# Kasli_SOC_IDC_EXT_Connectors.net
KiCad netlist of a schematic drawn in Altium Designer
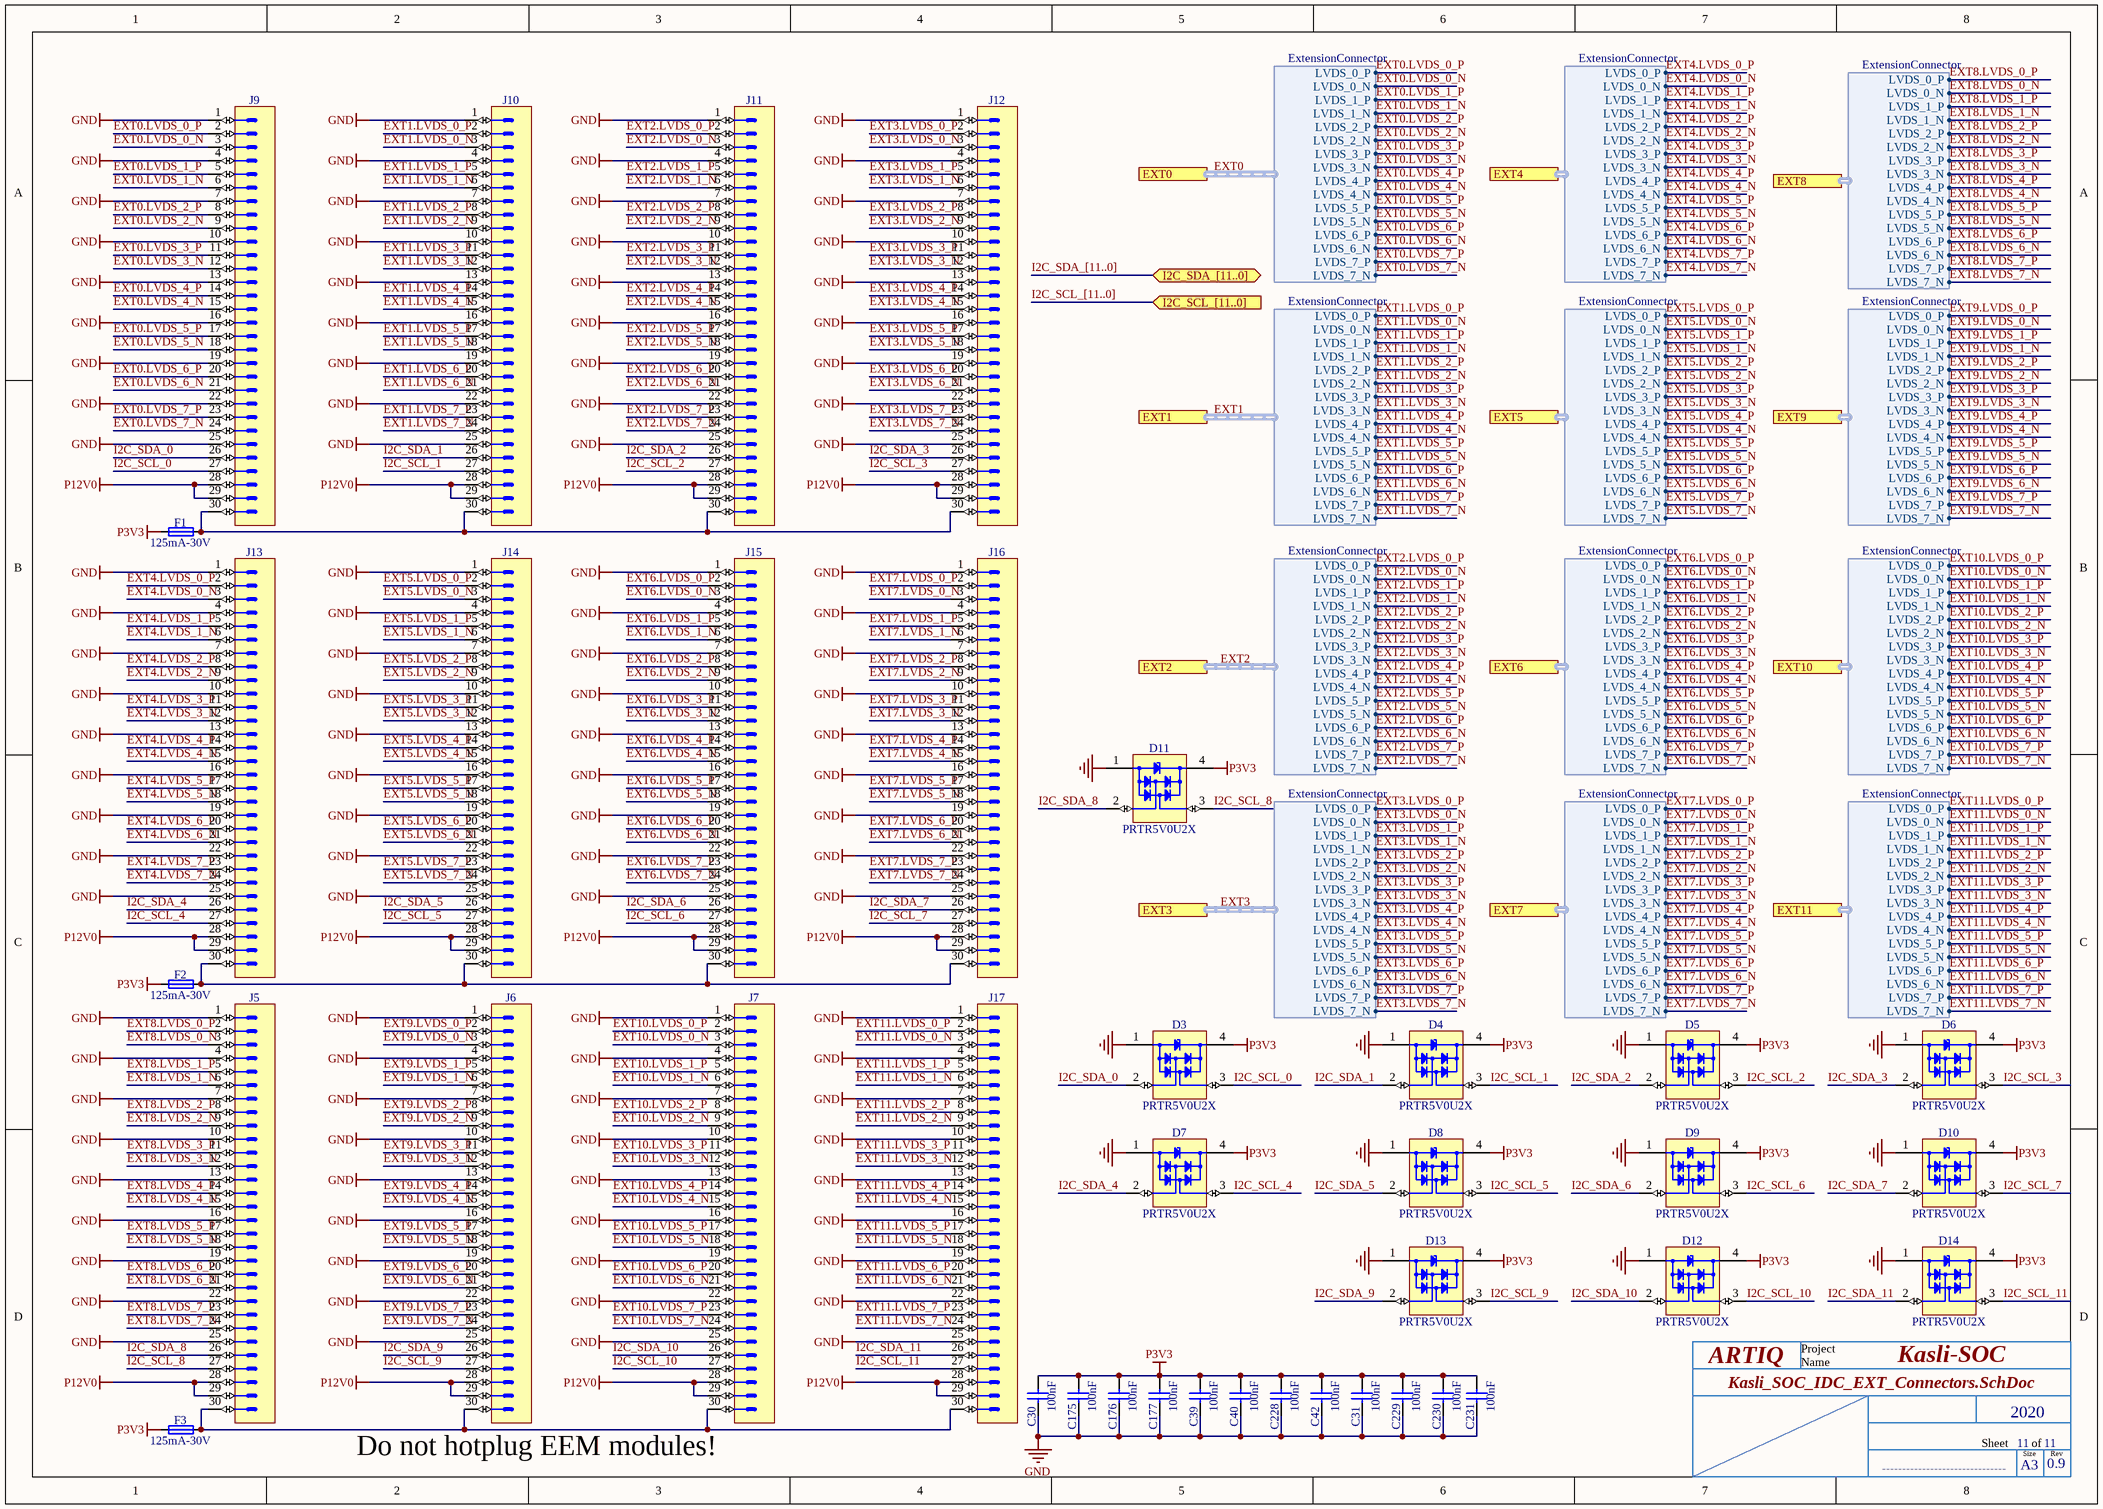
[diagram p0: Kasli_SOC_IDC_EXT_Connectors.SchDoc]

(export (version "E")
  (design (tool "Eeschema 10.0.6"))
  (components
    (comp (ref "C30")
      (value "100nF")
      (footprint "CAPC0603X33N")
      (description "Non-polarised capacitor")
      (fields
        (field (name "PART NUMBER") "CC0201_100NF_6.3V_10%_X5R")
        (field (name "VOLTAGE") "6.3V")
        (field (name "AUTHOR") "CERN DEM JLC")
      )
      (libsource (lib "Capacitors") (part "Capacitor - non polarized"))
    )
    (comp (ref "C31")
      (value "100nF")
      (footprint "CAPC0603X33N")
      (description "Non-polarised capacitor")
      (fields
        (field (name "PART NUMBER") "CC0201_100NF_6.3V_10%_X5R")
        (field (name "VOLTAGE") "6.3V")
        (field (name "AUTHOR") "CERN DEM JLC")
      )
      (libsource (lib "Capacitors") (part "Capacitor - non polarized"))
    )
    (comp (ref "C39")
      (value "100nF")
      (footprint "CAPC0603X33N")
      (description "Non-polarised capacitor")
      (fields
        (field (name "PART NUMBER") "CC0201_100NF_6.3V_10%_X5R")
        (field (name "VOLTAGE") "6.3V")
        (field (name "AUTHOR") "CERN DEM JLC")
      )
      (libsource (lib "Capacitors") (part "Capacitor - non polarized"))
    )
    (comp (ref "C40")
      (value "100nF")
      (footprint "CAPC0603X33N")
      (description "Non-polarised capacitor")
      (fields
        (field (name "PART NUMBER") "CC0201_100NF_6.3V_10%_X5R")
        (field (name "VOLTAGE") "6.3V")
        (field (name "AUTHOR") "CERN DEM JLC")
      )
      (libsource (lib "Capacitors") (part "Capacitor - non polarized"))
    )
    (comp (ref "C42")
      (value "100nF")
      (footprint "CAPC0603X33N")
      (description "Non-polarised capacitor")
      (fields
        (field (name "PART NUMBER") "CC0201_100NF_6.3V_10%_X5R")
        (field (name "VOLTAGE") "6.3V")
        (field (name "AUTHOR") "CERN DEM JLC")
      )
      (libsource (lib "Capacitors") (part "Capacitor - non polarized"))
    )
    (comp (ref "C175")
      (value "100nF")
      (footprint "CAPC0603X33N")
      (description "Non-polarised capacitor")
      (fields
        (field (name "PART NUMBER") "CC0201_100NF_6.3V_10%_X5R")
        (field (name "VOLTAGE") "6.3V")
        (field (name "AUTHOR") "CERN DEM JLC")
      )
      (libsource (lib "Capacitors") (part "Capacitor - non polarized"))
    )
    (comp (ref "C176")
      (value "100nF")
      (footprint "CAPC0603X33N")
      (description "Non-polarised capacitor")
      (fields
        (field (name "PART NUMBER") "CC0201_100NF_6.3V_10%_X5R")
        (field (name "VOLTAGE") "6.3V")
        (field (name "AUTHOR") "CERN DEM JLC")
      )
      (libsource (lib "Capacitors") (part "Capacitor - non polarized"))
    )
    (comp (ref "C177")
      (value "100nF")
      (footprint "CAPC0603X33N")
      (description "Non-polarised capacitor")
      (fields
        (field (name "PART NUMBER") "CC0201_100NF_6.3V_10%_X5R")
        (field (name "VOLTAGE") "6.3V")
        (field (name "AUTHOR") "CERN DEM JLC")
      )
      (libsource (lib "Capacitors") (part "Capacitor - non polarized"))
    )
    (comp (ref "C228")
      (value "100nF")
      (footprint "CAPC0603X33N")
      (description "Non-polarised capacitor")
      (fields
        (field (name "PART NUMBER") "CC0201_100NF_6.3V_10%_X5R")
        (field (name "VOLTAGE") "6.3V")
        (field (name "AUTHOR") "CERN DEM JLC")
      )
      (libsource (lib "Capacitors") (part "Capacitor - non polarized"))
    )
    (comp (ref "C229")
      (value "100nF")
      (footprint "CAPC0603X33N")
      (description "Non-polarised capacitor")
      (fields
        (field (name "PART NUMBER") "CC0201_100NF_6.3V_10%_X5R")
        (field (name "VOLTAGE") "6.3V")
        (field (name "AUTHOR") "CERN DEM JLC")
      )
      (libsource (lib "Capacitors") (part "Capacitor - non polarized"))
    )
    (comp (ref "C230")
      (value "100nF")
      (footprint "CAPC0603X33N")
      (description "Non-polarised capacitor")
      (fields
        (field (name "PART NUMBER") "CC0201_100NF_6.3V_10%_X5R")
        (field (name "VOLTAGE") "6.3V")
        (field (name "AUTHOR") "CERN DEM JLC")
      )
      (libsource (lib "Capacitors") (part "Capacitor - non polarized"))
    )
    (comp (ref "C231")
      (value "100nF")
      (footprint "CAPC0603X33N")
      (description "Non-polarised capacitor")
      (fields
        (field (name "PART NUMBER") "CC0201_100NF_6.3V_10%_X5R")
        (field (name "VOLTAGE") "6.3V")
        (field (name "AUTHOR") "CERN DEM JLC")
      )
      (libsource (lib "Capacitors") (part "Capacitor - non polarized"))
    )
    (comp (ref "D3")
      (value "PRTR5V0U2X")
      (footprint "SOT190P230X110-4N")
      (description "Ultra Low Capacitance Double Rail-to-Rail ESD Protection Diode")
      (fields
        (field (name "VOLTAGE") "5.5V")
        (field (name "MANUFACTURER") "NXP SEMICONDUCTORS")
        (field (name "AUTHOR") "CERN DEM JLC")
      )
      (libsource (lib "ICs And Semiconductors") (part "PRTR5V0U2X"))
    )
    (comp (ref "D4")
      (value "PRTR5V0U2X")
      (footprint "SOT190P230X110-4N")
      (description "Ultra Low Capacitance Double Rail-to-Rail ESD Protection Diode")
      (fields
        (field (name "VOLTAGE") "5.5V")
        (field (name "MANUFACTURER") "NXP SEMICONDUCTORS")
        (field (name "AUTHOR") "CERN DEM JLC")
      )
      (libsource (lib "ICs And Semiconductors") (part "PRTR5V0U2X"))
    )
    (comp (ref "D5")
      (value "PRTR5V0U2X")
      (footprint "SOT190P230X110-4N")
      (description "Ultra Low Capacitance Double Rail-to-Rail ESD Protection Diode")
      (fields
        (field (name "VOLTAGE") "5.5V")
        (field (name "MANUFACTURER") "NXP SEMICONDUCTORS")
        (field (name "AUTHOR") "CERN DEM JLC")
      )
      (libsource (lib "ICs And Semiconductors") (part "PRTR5V0U2X"))
    )
    (comp (ref "D6")
      (value "PRTR5V0U2X")
      (footprint "SOT190P230X110-4N")
      (description "Ultra Low Capacitance Double Rail-to-Rail ESD Protection Diode")
      (fields
        (field (name "VOLTAGE") "5.5V")
        (field (name "MANUFACTURER") "NXP SEMICONDUCTORS")
        (field (name "AUTHOR") "CERN DEM JLC")
      )
      (libsource (lib "ICs And Semiconductors") (part "PRTR5V0U2X"))
    )
    (comp (ref "D7")
      (value "PRTR5V0U2X")
      (footprint "SOT190P230X110-4N")
      (description "Ultra Low Capacitance Double Rail-to-Rail ESD Protection Diode")
      (fields
        (field (name "VOLTAGE") "5.5V")
        (field (name "MANUFACTURER") "NXP SEMICONDUCTORS")
        (field (name "AUTHOR") "CERN DEM JLC")
      )
      (libsource (lib "ICs And Semiconductors") (part "PRTR5V0U2X"))
    )
    (comp (ref "D8")
      (value "PRTR5V0U2X")
      (footprint "SOT190P230X110-4N")
      (description "Ultra Low Capacitance Double Rail-to-Rail ESD Protection Diode")
      (fields
        (field (name "VOLTAGE") "5.5V")
        (field (name "MANUFACTURER") "NXP SEMICONDUCTORS")
        (field (name "AUTHOR") "CERN DEM JLC")
      )
      (libsource (lib "ICs And Semiconductors") (part "PRTR5V0U2X"))
    )
    (comp (ref "D9")
      (value "PRTR5V0U2X")
      (footprint "SOT190P230X110-4N")
      (description "Ultra Low Capacitance Double Rail-to-Rail ESD Protection Diode")
      (fields
        (field (name "VOLTAGE") "5.5V")
        (field (name "MANUFACTURER") "NXP SEMICONDUCTORS")
        (field (name "AUTHOR") "CERN DEM JLC")
      )
      (libsource (lib "ICs And Semiconductors") (part "PRTR5V0U2X"))
    )
    (comp (ref "D10")
      (value "PRTR5V0U2X")
      (footprint "SOT190P230X110-4N")
      (description "Ultra Low Capacitance Double Rail-to-Rail ESD Protection Diode")
      (fields
        (field (name "VOLTAGE") "5.5V")
        (field (name "MANUFACTURER") "NXP SEMICONDUCTORS")
        (field (name "AUTHOR") "CERN DEM JLC")
      )
      (libsource (lib "ICs And Semiconductors") (part "PRTR5V0U2X"))
    )
    (comp (ref "D11")
      (value "PRTR5V0U2X")
      (footprint "SOT190P230X110-4N")
      (description "Ultra Low Capacitance Double Rail-to-Rail ESD Protection Diode")
      (fields
        (field (name "VOLTAGE") "5.5V")
        (field (name "MANUFACTURER") "NXP SEMICONDUCTORS")
        (field (name "AUTHOR") "CERN DEM JLC")
      )
      (libsource (lib "ICs And Semiconductors") (part "PRTR5V0U2X"))
    )
    (comp (ref "D12")
      (value "PRTR5V0U2X")
      (footprint "SOT190P230X110-4N")
      (description "Ultra Low Capacitance Double Rail-to-Rail ESD Protection Diode")
      (fields
        (field (name "VOLTAGE") "5.5V")
        (field (name "MANUFACTURER") "NXP SEMICONDUCTORS")
        (field (name "AUTHOR") "CERN DEM JLC")
      )
      (libsource (lib "ICs And Semiconductors") (part "PRTR5V0U2X"))
    )
    (comp (ref "D13")
      (value "PRTR5V0U2X")
      (footprint "SOT190P230X110-4N")
      (description "Ultra Low Capacitance Double Rail-to-Rail ESD Protection Diode")
      (fields
        (field (name "VOLTAGE") "5.5V")
        (field (name "MANUFACTURER") "NXP SEMICONDUCTORS")
        (field (name "AUTHOR") "CERN DEM JLC")
      )
      (libsource (lib "ICs And Semiconductors") (part "PRTR5V0U2X"))
    )
    (comp (ref "D14")
      (value "PRTR5V0U2X")
      (footprint "SOT190P230X110-4N")
      (description "Ultra Low Capacitance Double Rail-to-Rail ESD Protection Diode")
      (fields
        (field (name "VOLTAGE") "5.5V")
        (field (name "MANUFACTURER") "NXP SEMICONDUCTORS")
        (field (name "AUTHOR") "CERN DEM JLC")
      )
      (libsource (lib "ICs And Semiconductors") (part "PRTR5V0U2X"))
    )
    (comp (ref "F1")
      (value "125mA-30V")
      (footprint "FUSR_LITTELFUSE_1206L012")
      (description "Fuse")
      (fields
        (field (name "PART NUMBER") "FUSR_LITTELFUSE_1206L012")
        (field (name "MANUFACTURER") "LITTELFUSE")
        (field (name "AUTHOR") "CERN DEM JLC")
      )
      (libsource (lib "Eletro-mechanical") (part "Fuse"))
    )
    (comp (ref "F2")
      (value "125mA-30V")
      (footprint "FUSR_LITTELFUSE_1206L012")
      (description "Fuse")
      (fields
        (field (name "PART NUMBER") "FUSR_LITTELFUSE_1206L012")
        (field (name "MANUFACTURER") "LITTELFUSE")
        (field (name "AUTHOR") "CERN DEM JLC")
      )
      (libsource (lib "Eletro-mechanical") (part "Fuse"))
    )
    (comp (ref "F3")
      (value "125mA-30V")
      (footprint "FUSR_LITTELFUSE_1206L012")
      (description "Fuse")
      (fields
        (field (name "PART NUMBER") "FUSR_LITTELFUSE_1206L012")
        (field (name "MANUFACTURER") "LITTELFUSE")
        (field (name "AUTHOR") "CERN DEM JLC")
      )
      (libsource (lib "Eletro-mechanical") (part "Fuse"))
    )
    (comp (ref "J5")
      (value "~")
      (footprint "3M_N2530-6002RB")
      (description "Connector 30 Male")
      (fields
        (field (name "PART NUMBER") "3M_N2530-6002RB")
        (field (name "MANUFACTURER") "3M")
        (field (name "AUTHOR") "CERN DEM JLC")
      )
      (libsource (lib "Connectors") (part "Connector 30 Male"))
    )
    (comp (ref "J6")
      (value "~")
      (footprint "3M_N2530-6002RB")
      (description "Connector 30 Male")
      (fields
        (field (name "PART NUMBER") "3M_N2530-6002RB")
        (field (name "MANUFACTURER") "3M")
        (field (name "AUTHOR") "CERN DEM JLC")
      )
      (libsource (lib "Connectors") (part "Connector 30 Male"))
    )
    (comp (ref "J7")
      (value "~")
      (footprint "3M_N2530-6002RB")
      (description "Connector 30 Male")
      (fields
        (field (name "PART NUMBER") "3M_N2530-6002RB")
        (field (name "MANUFACTURER") "3M")
        (field (name "AUTHOR") "CERN DEM JLC")
      )
      (libsource (lib "Connectors") (part "Connector 30 Male"))
    )
    (comp (ref "J9")
      (value "~")
      (footprint "3M_N2530-6002RB")
      (description "Connector 30 Male")
      (fields
        (field (name "PART NUMBER") "3M_N2530-6002RB")
        (field (name "MANUFACTURER") "3M")
        (field (name "AUTHOR") "CERN DEM JLC")
      )
      (libsource (lib "Connectors") (part "Connector 30 Male"))
    )
    (comp (ref "J10")
      (value "~")
      (footprint "3M_N2530-6002RB")
      (description "Connector 30 Male")
      (fields
        (field (name "PART NUMBER") "3M_N2530-6002RB")
        (field (name "MANUFACTURER") "3M")
        (field (name "AUTHOR") "CERN DEM JLC")
      )
      (libsource (lib "Connectors") (part "Connector 30 Male"))
    )
    (comp (ref "J11")
      (value "~")
      (footprint "3M_N2530-6002RB")
      (description "Connector 30 Male")
      (fields
        (field (name "PART NUMBER") "3M_N2530-6002RB")
        (field (name "MANUFACTURER") "3M")
        (field (name "AUTHOR") "CERN DEM JLC")
      )
      (libsource (lib "Connectors") (part "Connector 30 Male"))
    )
    (comp (ref "J12")
      (value "~")
      (footprint "3M_N2530-6002RB")
      (description "Connector 30 Male")
      (fields
        (field (name "PART NUMBER") "3M_N2530-6002RB")
        (field (name "MANUFACTURER") "3M")
        (field (name "AUTHOR") "CERN DEM JLC")
      )
      (libsource (lib "Connectors") (part "Connector 30 Male"))
    )
    (comp (ref "J13")
      (value "~")
      (footprint "3M_N2530-6002RB")
      (description "Connector 30 Male")
      (fields
        (field (name "PART NUMBER") "3M_N2530-6002RB")
        (field (name "MANUFACTURER") "3M")
        (field (name "AUTHOR") "CERN DEM JLC")
      )
      (libsource (lib "Connectors") (part "Connector 30 Male"))
    )
    (comp (ref "J14")
      (value "~")
      (footprint "3M_N2530-6002RB")
      (description "Connector 30 Male")
      (fields
        (field (name "PART NUMBER") "3M_N2530-6002RB")
        (field (name "MANUFACTURER") "3M")
        (field (name "AUTHOR") "CERN DEM JLC")
      )
      (libsource (lib "Connectors") (part "Connector 30 Male"))
    )
    (comp (ref "J15")
      (value "~")
      (footprint "3M_N2530-6002RB")
      (description "Connector 30 Male")
      (fields
        (field (name "PART NUMBER") "3M_N2530-6002RB")
        (field (name "MANUFACTURER") "3M")
        (field (name "AUTHOR") "CERN DEM JLC")
      )
      (libsource (lib "Connectors") (part "Connector 30 Male"))
    )
    (comp (ref "J16")
      (value "~")
      (footprint "3M_N2530-6002RB")
      (description "Connector 30 Male")
      (fields
        (field (name "PART NUMBER") "3M_N2530-6002RB")
        (field (name "MANUFACTURER") "3M")
        (field (name "AUTHOR") "CERN DEM JLC")
      )
      (libsource (lib "Connectors") (part "Connector 30 Male"))
    )
    (comp (ref "J17")
      (value "~")
      (footprint "3M_N2530-6002RB")
      (description "Connector 30 Male")
      (fields
        (field (name "PART NUMBER") "3M_N2530-6002RB")
        (field (name "MANUFACTURER") "3M")
        (field (name "AUTHOR") "CERN DEM JLC")
      )
      (libsource (lib "Connectors") (part "Connector 30 Male"))
    )
  )
  (nets
    (net (code "6") (name "/EXT0.LVDS_0_N") (class "Default")
      (node (ref "J9") (pin "3") (pinfunction "3_3") (pintype "bidirectional"))
    )
    (net (code "7") (name "/EXT0.LVDS_0_P") (class "Default")
      (node (ref "J9") (pin "2") (pinfunction "2_2") (pintype "bidirectional"))
    )
    (net (code "8") (name "/EXT0.LVDS_1_N") (class "Default")
      (node (ref "J9") (pin "6") (pinfunction "6_6") (pintype "bidirectional"))
    )
    (net (code "9") (name "/EXT0.LVDS_1_P") (class "Default")
      (node (ref "J9") (pin "5") (pinfunction "5_5") (pintype "bidirectional"))
    )
    (net (code "10") (name "/EXT0.LVDS_2_N") (class "Default")
      (node (ref "J9") (pin "9") (pinfunction "9_9") (pintype "bidirectional"))
    )
    (net (code "11") (name "/EXT0.LVDS_2_P") (class "Default")
      (node (ref "J9") (pin "8") (pinfunction "8_8") (pintype "bidirectional"))
    )
    (net (code "12") (name "/EXT0.LVDS_3_N") (class "Default")
      (node (ref "J9") (pin "12") (pinfunction "12_12") (pintype "bidirectional"))
    )
    (net (code "13") (name "/EXT0.LVDS_3_P") (class "Default")
      (node (ref "J9") (pin "11") (pinfunction "11_11") (pintype "bidirectional"))
    )
    (net (code "14") (name "/EXT0.LVDS_4_N") (class "Default")
      (node (ref "J9") (pin "15") (pinfunction "15_15") (pintype "bidirectional"))
    )
    (net (code "15") (name "/EXT0.LVDS_4_P") (class "Default")
      (node (ref "J9") (pin "14") (pinfunction "14_14") (pintype "bidirectional"))
    )
    (net (code "16") (name "/EXT0.LVDS_5_N") (class "Default")
      (node (ref "J9") (pin "18") (pinfunction "18_18") (pintype "bidirectional"))
    )
    (net (code "17") (name "/EXT0.LVDS_5_P") (class "Default")
      (node (ref "J9") (pin "17") (pinfunction "17_17") (pintype "bidirectional"))
    )
    (net (code "18") (name "/EXT0.LVDS_6_N") (class "Default")
      (node (ref "J9") (pin "21") (pinfunction "21_21") (pintype "bidirectional"))
    )
    (net (code "19") (name "/EXT0.LVDS_6_P") (class "Default")
      (node (ref "J9") (pin "20") (pinfunction "20_20") (pintype "bidirectional"))
    )
    (net (code "20") (name "/EXT0.LVDS_7_N") (class "Default")
      (node (ref "J9") (pin "24") (pinfunction "24_24") (pintype "bidirectional"))
    )
    (net (code "21") (name "/EXT0.LVDS_7_P") (class "Default")
      (node (ref "J9") (pin "23") (pinfunction "23_23") (pintype "bidirectional"))
    )
    (net (code "23") (name "/EXT1.LVDS_0_N") (class "Default")
      (node (ref "J10") (pin "3") (pinfunction "3_3") (pintype "bidirectional"))
    )
    (net (code "24") (name "/EXT1.LVDS_0_P") (class "Default")
      (node (ref "J10") (pin "2") (pinfunction "2_2") (pintype "bidirectional"))
    )
    (net (code "25") (name "/EXT1.LVDS_1_N") (class "Default")
      (node (ref "J10") (pin "6") (pinfunction "6_6") (pintype "bidirectional"))
    )
    (net (code "26") (name "/EXT1.LVDS_1_P") (class "Default")
      (node (ref "J10") (pin "5") (pinfunction "5_5") (pintype "bidirectional"))
    )
    (net (code "27") (name "/EXT1.LVDS_2_N") (class "Default")
      (node (ref "J10") (pin "9") (pinfunction "9_9") (pintype "bidirectional"))
    )
    (net (code "28") (name "/EXT1.LVDS_2_P") (class "Default")
      (node (ref "J10") (pin "8") (pinfunction "8_8") (pintype "bidirectional"))
    )
    (net (code "29") (name "/EXT1.LVDS_3_N") (class "Default")
      (node (ref "J10") (pin "12") (pinfunction "12_12") (pintype "bidirectional"))
    )
    (net (code "30") (name "/EXT1.LVDS_3_P") (class "Default")
      (node (ref "J10") (pin "11") (pinfunction "11_11") (pintype "bidirectional"))
    )
    (net (code "31") (name "/EXT1.LVDS_4_N") (class "Default")
      (node (ref "J10") (pin "15") (pinfunction "15_15") (pintype "bidirectional"))
    )
    (net (code "32") (name "/EXT1.LVDS_4_P") (class "Default")
      (node (ref "J10") (pin "14") (pinfunction "14_14") (pintype "bidirectional"))
    )
    (net (code "33") (name "/EXT1.LVDS_5_N") (class "Default")
      (node (ref "J10") (pin "18") (pinfunction "18_18") (pintype "bidirectional"))
    )
    (net (code "34") (name "/EXT1.LVDS_5_P") (class "Default")
      (node (ref "J10") (pin "17") (pinfunction "17_17") (pintype "bidirectional"))
    )
    (net (code "35") (name "/EXT1.LVDS_6_N") (class "Default")
      (node (ref "J10") (pin "21") (pinfunction "21_21") (pintype "bidirectional"))
    )
    (net (code "36") (name "/EXT1.LVDS_6_P") (class "Default")
      (node (ref "J10") (pin "20") (pinfunction "20_20") (pintype "bidirectional"))
    )
    (net (code "37") (name "/EXT1.LVDS_7_N") (class "Default")
      (node (ref "J10") (pin "24") (pinfunction "24_24") (pintype "bidirectional"))
    )
    (net (code "38") (name "/EXT1.LVDS_7_P") (class "Default")
      (node (ref "J10") (pin "23") (pinfunction "23_23") (pintype "bidirectional"))
    )
    (net (code "40") (name "/EXT2.LVDS_0_N") (class "Default")
      (node (ref "J11") (pin "3") (pinfunction "3_3") (pintype "bidirectional"))
    )
    (net (code "41") (name "/EXT2.LVDS_0_P") (class "Default")
      (node (ref "J11") (pin "2") (pinfunction "2_2") (pintype "bidirectional"))
    )
    (net (code "42") (name "/EXT2.LVDS_1_N") (class "Default")
      (node (ref "J11") (pin "6") (pinfunction "6_6") (pintype "bidirectional"))
    )
    (net (code "43") (name "/EXT2.LVDS_1_P") (class "Default")
      (node (ref "J11") (pin "5") (pinfunction "5_5") (pintype "bidirectional"))
    )
    (net (code "44") (name "/EXT2.LVDS_2_N") (class "Default")
      (node (ref "J11") (pin "9") (pinfunction "9_9") (pintype "bidirectional"))
    )
    (net (code "45") (name "/EXT2.LVDS_2_P") (class "Default")
      (node (ref "J11") (pin "8") (pinfunction "8_8") (pintype "bidirectional"))
    )
    (net (code "46") (name "/EXT2.LVDS_3_N") (class "Default")
      (node (ref "J11") (pin "12") (pinfunction "12_12") (pintype "bidirectional"))
    )
    (net (code "47") (name "/EXT2.LVDS_3_P") (class "Default")
      (node (ref "J11") (pin "11") (pinfunction "11_11") (pintype "bidirectional"))
    )
    (net (code "48") (name "/EXT2.LVDS_4_N") (class "Default")
      (node (ref "J11") (pin "15") (pinfunction "15_15") (pintype "bidirectional"))
    )
    (net (code "49") (name "/EXT2.LVDS_4_P") (class "Default")
      (node (ref "J11") (pin "14") (pinfunction "14_14") (pintype "bidirectional"))
    )
    (net (code "50") (name "/EXT2.LVDS_5_N") (class "Default")
      (node (ref "J11") (pin "18") (pinfunction "18_18") (pintype "bidirectional"))
    )
    (net (code "51") (name "/EXT2.LVDS_5_P") (class "Default")
      (node (ref "J11") (pin "17") (pinfunction "17_17") (pintype "bidirectional"))
    )
    (net (code "52") (name "/EXT2.LVDS_6_N") (class "Default")
      (node (ref "J11") (pin "21") (pinfunction "21_21") (pintype "bidirectional"))
    )
    (net (code "53") (name "/EXT2.LVDS_6_P") (class "Default")
      (node (ref "J11") (pin "20") (pinfunction "20_20") (pintype "bidirectional"))
    )
    (net (code "54") (name "/EXT2.LVDS_7_N") (class "Default")
      (node (ref "J11") (pin "24") (pinfunction "24_24") (pintype "bidirectional"))
    )
    (net (code "55") (name "/EXT2.LVDS_7_P") (class "Default")
      (node (ref "J11") (pin "23") (pinfunction "23_23") (pintype "bidirectional"))
    )
    (net (code "57") (name "/EXT3.LVDS_0_N") (class "Default")
      (node (ref "J12") (pin "3") (pinfunction "3_3") (pintype "bidirectional"))
    )
    (net (code "58") (name "/EXT3.LVDS_0_P") (class "Default")
      (node (ref "J12") (pin "2") (pinfunction "2_2") (pintype "bidirectional"))
    )
    (net (code "59") (name "/EXT3.LVDS_1_N") (class "Default")
      (node (ref "J12") (pin "6") (pinfunction "6_6") (pintype "bidirectional"))
    )
    (net (code "60") (name "/EXT3.LVDS_1_P") (class "Default")
      (node (ref "J12") (pin "5") (pinfunction "5_5") (pintype "bidirectional"))
    )
    (net (code "61") (name "/EXT3.LVDS_2_N") (class "Default")
      (node (ref "J12") (pin "9") (pinfunction "9_9") (pintype "bidirectional"))
    )
    (net (code "62") (name "/EXT3.LVDS_2_P") (class "Default")
      (node (ref "J12") (pin "8") (pinfunction "8_8") (pintype "bidirectional"))
    )
    (net (code "63") (name "/EXT3.LVDS_3_N") (class "Default")
      (node (ref "J12") (pin "12") (pinfunction "12_12") (pintype "bidirectional"))
    )
    (net (code "64") (name "/EXT3.LVDS_3_P") (class "Default")
      (node (ref "J12") (pin "11") (pinfunction "11_11") (pintype "bidirectional"))
    )
    (net (code "65") (name "/EXT3.LVDS_4_N") (class "Default")
      (node (ref "J12") (pin "15") (pinfunction "15_15") (pintype "bidirectional"))
    )
    (net (code "66") (name "/EXT3.LVDS_4_P") (class "Default")
      (node (ref "J12") (pin "14") (pinfunction "14_14") (pintype "bidirectional"))
    )
    (net (code "67") (name "/EXT3.LVDS_5_N") (class "Default")
      (node (ref "J12") (pin "18") (pinfunction "18_18") (pintype "bidirectional"))
    )
    (net (code "68") (name "/EXT3.LVDS_5_P") (class "Default")
      (node (ref "J12") (pin "17") (pinfunction "17_17") (pintype "bidirectional"))
    )
    (net (code "69") (name "/EXT3.LVDS_6_N") (class "Default")
      (node (ref "J12") (pin "21") (pinfunction "21_21") (pintype "bidirectional"))
    )
    (net (code "70") (name "/EXT3.LVDS_6_P") (class "Default")
      (node (ref "J12") (pin "20") (pinfunction "20_20") (pintype "bidirectional"))
    )
    (net (code "71") (name "/EXT3.LVDS_7_N") (class "Default")
      (node (ref "J12") (pin "24") (pinfunction "24_24") (pintype "bidirectional"))
    )
    (net (code "72") (name "/EXT3.LVDS_7_P") (class "Default")
      (node (ref "J12") (pin "23") (pinfunction "23_23") (pintype "bidirectional"))
    )
    (net (code "74") (name "/EXT4.LVDS_0_N") (class "Default")
      (node (ref "J13") (pin "3") (pinfunction "3_3") (pintype "bidirectional"))
    )
    (net (code "75") (name "/EXT4.LVDS_0_P") (class "Default")
      (node (ref "J13") (pin "2") (pinfunction "2_2") (pintype "bidirectional"))
    )
    (net (code "76") (name "/EXT4.LVDS_1_N") (class "Default")
      (node (ref "J13") (pin "6") (pinfunction "6_6") (pintype "bidirectional"))
    )
    (net (code "77") (name "/EXT4.LVDS_1_P") (class "Default")
      (node (ref "J13") (pin "5") (pinfunction "5_5") (pintype "bidirectional"))
    )
    (net (code "78") (name "/EXT4.LVDS_2_N") (class "Default")
      (node (ref "J13") (pin "9") (pinfunction "9_9") (pintype "bidirectional"))
    )
    (net (code "79") (name "/EXT4.LVDS_2_P") (class "Default")
      (node (ref "J13") (pin "8") (pinfunction "8_8") (pintype "bidirectional"))
    )
    (net (code "80") (name "/EXT4.LVDS_3_N") (class "Default")
      (node (ref "J13") (pin "12") (pinfunction "12_12") (pintype "bidirectional"))
    )
    (net (code "81") (name "/EXT4.LVDS_3_P") (class "Default")
      (node (ref "J13") (pin "11") (pinfunction "11_11") (pintype "bidirectional"))
    )
    (net (code "82") (name "/EXT4.LVDS_4_N") (class "Default")
      (node (ref "J13") (pin "15") (pinfunction "15_15") (pintype "bidirectional"))
    )
    (net (code "83") (name "/EXT4.LVDS_4_P") (class "Default")
      (node (ref "J13") (pin "14") (pinfunction "14_14") (pintype "bidirectional"))
    )
    (net (code "84") (name "/EXT4.LVDS_5_N") (class "Default")
      (node (ref "J13") (pin "18") (pinfunction "18_18") (pintype "bidirectional"))
    )
    (net (code "85") (name "/EXT4.LVDS_5_P") (class "Default")
      (node (ref "J13") (pin "17") (pinfunction "17_17") (pintype "bidirectional"))
    )
    (net (code "86") (name "/EXT4.LVDS_6_N") (class "Default")
      (node (ref "J13") (pin "21") (pinfunction "21_21") (pintype "bidirectional"))
    )
    (net (code "87") (name "/EXT4.LVDS_6_P") (class "Default")
      (node (ref "J13") (pin "20") (pinfunction "20_20") (pintype "bidirectional"))
    )
    (net (code "88") (name "/EXT4.LVDS_7_N") (class "Default")
      (node (ref "J13") (pin "24") (pinfunction "24_24") (pintype "bidirectional"))
    )
    (net (code "89") (name "/EXT4.LVDS_7_P") (class "Default")
      (node (ref "J13") (pin "23") (pinfunction "23_23") (pintype "bidirectional"))
    )
    (net (code "90") (name "/EXT5.LVDS_0_N") (class "Default")
      (node (ref "J14") (pin "3") (pinfunction "3_3") (pintype "bidirectional"))
    )
    (net (code "91") (name "/EXT5.LVDS_0_P") (class "Default")
      (node (ref "J14") (pin "2") (pinfunction "2_2") (pintype "bidirectional"))
    )
    (net (code "92") (name "/EXT5.LVDS_1_N") (class "Default")
      (node (ref "J14") (pin "6") (pinfunction "6_6") (pintype "bidirectional"))
    )
    (net (code "93") (name "/EXT5.LVDS_1_P") (class "Default")
      (node (ref "J14") (pin "5") (pinfunction "5_5") (pintype "bidirectional"))
    )
    (net (code "94") (name "/EXT5.LVDS_2_N") (class "Default")
      (node (ref "J14") (pin "9") (pinfunction "9_9") (pintype "bidirectional"))
    )
    (net (code "95") (name "/EXT5.LVDS_2_P") (class "Default")
      (node (ref "J14") (pin "8") (pinfunction "8_8") (pintype "bidirectional"))
    )
    (net (code "96") (name "/EXT5.LVDS_3_N") (class "Default")
      (node (ref "J14") (pin "12") (pinfunction "12_12") (pintype "bidirectional"))
    )
    (net (code "97") (name "/EXT5.LVDS_3_P") (class "Default")
      (node (ref "J14") (pin "11") (pinfunction "11_11") (pintype "bidirectional"))
    )
    (net (code "98") (name "/EXT5.LVDS_4_N") (class "Default")
      (node (ref "J14") (pin "15") (pinfunction "15_15") (pintype "bidirectional"))
    )
    (net (code "99") (name "/EXT5.LVDS_4_P") (class "Default")
      (node (ref "J14") (pin "14") (pinfunction "14_14") (pintype "bidirectional"))
    )
    (net (code "100") (name "/EXT5.LVDS_5_N") (class "Default")
      (node (ref "J14") (pin "18") (pinfunction "18_18") (pintype "bidirectional"))
    )
    (net (code "101") (name "/EXT5.LVDS_5_P") (class "Default")
      (node (ref "J14") (pin "17") (pinfunction "17_17") (pintype "bidirectional"))
    )
    (net (code "102") (name "/EXT5.LVDS_6_N") (class "Default")
      (node (ref "J14") (pin "21") (pinfunction "21_21") (pintype "bidirectional"))
    )
    (net (code "103") (name "/EXT5.LVDS_6_P") (class "Default")
      (node (ref "J14") (pin "20") (pinfunction "20_20") (pintype "bidirectional"))
    )
    (net (code "104") (name "/EXT5.LVDS_7_N") (class "Default")
      (node (ref "J14") (pin "24") (pinfunction "24_24") (pintype "bidirectional"))
    )
    (net (code "105") (name "/EXT5.LVDS_7_P") (class "Default")
      (node (ref "J14") (pin "23") (pinfunction "23_23") (pintype "bidirectional"))
    )
    (net (code "106") (name "/EXT6.LVDS_0_N") (class "Default")
      (node (ref "J15") (pin "3") (pinfunction "3_3") (pintype "bidirectional"))
    )
    (net (code "107") (name "/EXT6.LVDS_0_P") (class "Default")
      (node (ref "J15") (pin "2") (pinfunction "2_2") (pintype "bidirectional"))
    )
    (net (code "108") (name "/EXT6.LVDS_1_N") (class "Default")
      (node (ref "J15") (pin "6") (pinfunction "6_6") (pintype "bidirectional"))
    )
    (net (code "109") (name "/EXT6.LVDS_1_P") (class "Default")
      (node (ref "J15") (pin "5") (pinfunction "5_5") (pintype "bidirectional"))
    )
    (net (code "110") (name "/EXT6.LVDS_2_N") (class "Default")
      (node (ref "J15") (pin "9") (pinfunction "9_9") (pintype "bidirectional"))
    )
    (net (code "111") (name "/EXT6.LVDS_2_P") (class "Default")
      (node (ref "J15") (pin "8") (pinfunction "8_8") (pintype "bidirectional"))
    )
    (net (code "112") (name "/EXT6.LVDS_3_N") (class "Default")
      (node (ref "J15") (pin "12") (pinfunction "12_12") (pintype "bidirectional"))
    )
    (net (code "113") (name "/EXT6.LVDS_3_P") (class "Default")
      (node (ref "J15") (pin "11") (pinfunction "11_11") (pintype "bidirectional"))
    )
    (net (code "114") (name "/EXT6.LVDS_4_N") (class "Default")
      (node (ref "J15") (pin "15") (pinfunction "15_15") (pintype "bidirectional"))
    )
    (net (code "115") (name "/EXT6.LVDS_4_P") (class "Default")
      (node (ref "J15") (pin "14") (pinfunction "14_14") (pintype "bidirectional"))
    )
    (net (code "116") (name "/EXT6.LVDS_5_N") (class "Default")
      (node (ref "J15") (pin "18") (pinfunction "18_18") (pintype "bidirectional"))
    )
    (net (code "117") (name "/EXT6.LVDS_5_P") (class "Default")
      (node (ref "J15") (pin "17") (pinfunction "17_17") (pintype "bidirectional"))
    )
    (net (code "118") (name "/EXT6.LVDS_6_N") (class "Default")
      (node (ref "J15") (pin "21") (pinfunction "21_21") (pintype "bidirectional"))
    )
    (net (code "119") (name "/EXT6.LVDS_6_P") (class "Default")
      (node (ref "J15") (pin "20") (pinfunction "20_20") (pintype "bidirectional"))
    )
    (net (code "120") (name "/EXT6.LVDS_7_N") (class "Default")
      (node (ref "J15") (pin "24") (pinfunction "24_24") (pintype "bidirectional"))
    )
    (net (code "121") (name "/EXT6.LVDS_7_P") (class "Default")
      (node (ref "J15") (pin "23") (pinfunction "23_23") (pintype "bidirectional"))
    )
    (net (code "122") (name "/EXT7.LVDS_0_N") (class "Default")
      (node (ref "J16") (pin "3") (pinfunction "3_3") (pintype "bidirectional"))
    )
    (net (code "123") (name "/EXT7.LVDS_0_P") (class "Default")
      (node (ref "J16") (pin "2") (pinfunction "2_2") (pintype "bidirectional"))
    )
    (net (code "124") (name "/EXT7.LVDS_1_N") (class "Default")
      (node (ref "J16") (pin "6") (pinfunction "6_6") (pintype "bidirectional"))
    )
    (net (code "125") (name "/EXT7.LVDS_1_P") (class "Default")
      (node (ref "J16") (pin "5") (pinfunction "5_5") (pintype "bidirectional"))
    )
    (net (code "126") (name "/EXT7.LVDS_2_N") (class "Default")
      (node (ref "J16") (pin "9") (pinfunction "9_9") (pintype "bidirectional"))
    )
    (net (code "127") (name "/EXT7.LVDS_2_P") (class "Default")
      (node (ref "J16") (pin "8") (pinfunction "8_8") (pintype "bidirectional"))
    )
    (net (code "128") (name "/EXT7.LVDS_3_N") (class "Default")
      (node (ref "J16") (pin "12") (pinfunction "12_12") (pintype "bidirectional"))
    )
    (net (code "129") (name "/EXT7.LVDS_3_P") (class "Default")
      (node (ref "J16") (pin "11") (pinfunction "11_11") (pintype "bidirectional"))
    )
    (net (code "130") (name "/EXT7.LVDS_4_N") (class "Default")
      (node (ref "J16") (pin "15") (pinfunction "15_15") (pintype "bidirectional"))
    )
    (net (code "131") (name "/EXT7.LVDS_4_P") (class "Default")
      (node (ref "J16") (pin "14") (pinfunction "14_14") (pintype "bidirectional"))
    )
    (net (code "132") (name "/EXT7.LVDS_5_N") (class "Default")
      (node (ref "J16") (pin "18") (pinfunction "18_18") (pintype "bidirectional"))
    )
    (net (code "133") (name "/EXT7.LVDS_5_P") (class "Default")
      (node (ref "J16") (pin "17") (pinfunction "17_17") (pintype "bidirectional"))
    )
    (net (code "134") (name "/EXT7.LVDS_6_N") (class "Default")
      (node (ref "J16") (pin "21") (pinfunction "21_21") (pintype "bidirectional"))
    )
    (net (code "135") (name "/EXT7.LVDS_6_P") (class "Default")
      (node (ref "J16") (pin "20") (pinfunction "20_20") (pintype "bidirectional"))
    )
    (net (code "136") (name "/EXT7.LVDS_7_N") (class "Default")
      (node (ref "J16") (pin "24") (pinfunction "24_24") (pintype "bidirectional"))
    )
    (net (code "137") (name "/EXT7.LVDS_7_P") (class "Default")
      (node (ref "J16") (pin "23") (pinfunction "23_23") (pintype "bidirectional"))
    )
    (net (code "138") (name "/EXT8.LVDS_0_N") (class "Default")
      (node (ref "J5") (pin "3") (pinfunction "3_3") (pintype "bidirectional"))
    )
    (net (code "139") (name "/EXT8.LVDS_0_P") (class "Default")
      (node (ref "J5") (pin "2") (pinfunction "2_2") (pintype "bidirectional"))
    )
    (net (code "140") (name "/EXT8.LVDS_1_N") (class "Default")
      (node (ref "J5") (pin "6") (pinfunction "6_6") (pintype "bidirectional"))
    )
    (net (code "141") (name "/EXT8.LVDS_1_P") (class "Default")
      (node (ref "J5") (pin "5") (pinfunction "5_5") (pintype "bidirectional"))
    )
    (net (code "142") (name "/EXT8.LVDS_2_N") (class "Default")
      (node (ref "J5") (pin "9") (pinfunction "9_9") (pintype "bidirectional"))
    )
    (net (code "143") (name "/EXT8.LVDS_2_P") (class "Default")
      (node (ref "J5") (pin "8") (pinfunction "8_8") (pintype "bidirectional"))
    )
    (net (code "144") (name "/EXT8.LVDS_3_N") (class "Default")
      (node (ref "J5") (pin "12") (pinfunction "12_12") (pintype "bidirectional"))
    )
    (net (code "145") (name "/EXT8.LVDS_3_P") (class "Default")
      (node (ref "J5") (pin "11") (pinfunction "11_11") (pintype "bidirectional"))
    )
    (net (code "146") (name "/EXT8.LVDS_4_N") (class "Default")
      (node (ref "J5") (pin "15") (pinfunction "15_15") (pintype "bidirectional"))
    )
    (net (code "147") (name "/EXT8.LVDS_4_P") (class "Default")
      (node (ref "J5") (pin "14") (pinfunction "14_14") (pintype "bidirectional"))
    )
    (net (code "148") (name "/EXT8.LVDS_5_N") (class "Default")
      (node (ref "J5") (pin "18") (pinfunction "18_18") (pintype "bidirectional"))
    )
    (net (code "149") (name "/EXT8.LVDS_5_P") (class "Default")
      (node (ref "J5") (pin "17") (pinfunction "17_17") (pintype "bidirectional"))
    )
    (net (code "150") (name "/EXT8.LVDS_6_N") (class "Default")
      (node (ref "J5") (pin "21") (pinfunction "21_21") (pintype "bidirectional"))
    )
    (net (code "151") (name "/EXT8.LVDS_6_P") (class "Default")
      (node (ref "J5") (pin "20") (pinfunction "20_20") (pintype "bidirectional"))
    )
    (net (code "152") (name "/EXT8.LVDS_7_N") (class "Default")
      (node (ref "J5") (pin "24") (pinfunction "24_24") (pintype "bidirectional"))
    )
    (net (code "153") (name "/EXT8.LVDS_7_P") (class "Default")
      (node (ref "J5") (pin "23") (pinfunction "23_23") (pintype "bidirectional"))
    )
    (net (code "154") (name "/EXT9.LVDS_0_N") (class "Default")
      (node (ref "J6") (pin "3") (pinfunction "3_3") (pintype "bidirectional"))
    )
    (net (code "155") (name "/EXT9.LVDS_0_P") (class "Default")
      (node (ref "J6") (pin "2") (pinfunction "2_2") (pintype "bidirectional"))
    )
    (net (code "156") (name "/EXT9.LVDS_1_N") (class "Default")
      (node (ref "J6") (pin "6") (pinfunction "6_6") (pintype "bidirectional"))
    )
    (net (code "157") (name "/EXT9.LVDS_1_P") (class "Default")
      (node (ref "J6") (pin "5") (pinfunction "5_5") (pintype "bidirectional"))
    )
    (net (code "158") (name "/EXT9.LVDS_2_N") (class "Default")
      (node (ref "J6") (pin "9") (pinfunction "9_9") (pintype "bidirectional"))
    )
    (net (code "159") (name "/EXT9.LVDS_2_P") (class "Default")
      (node (ref "J6") (pin "8") (pinfunction "8_8") (pintype "bidirectional"))
    )
    (net (code "160") (name "/EXT9.LVDS_3_N") (class "Default")
      (node (ref "J6") (pin "12") (pinfunction "12_12") (pintype "bidirectional"))
    )
    (net (code "161") (name "/EXT9.LVDS_3_P") (class "Default")
      (node (ref "J6") (pin "11") (pinfunction "11_11") (pintype "bidirectional"))
    )
    (net (code "162") (name "/EXT9.LVDS_4_N") (class "Default")
      (node (ref "J6") (pin "15") (pinfunction "15_15") (pintype "bidirectional"))
    )
    (net (code "163") (name "/EXT9.LVDS_4_P") (class "Default")
      (node (ref "J6") (pin "14") (pinfunction "14_14") (pintype "bidirectional"))
    )
    (net (code "164") (name "/EXT9.LVDS_5_N") (class "Default")
      (node (ref "J6") (pin "18") (pinfunction "18_18") (pintype "bidirectional"))
    )
    (net (code "165") (name "/EXT9.LVDS_5_P") (class "Default")
      (node (ref "J6") (pin "17") (pinfunction "17_17") (pintype "bidirectional"))
    )
    (net (code "166") (name "/EXT9.LVDS_6_N") (class "Default")
      (node (ref "J6") (pin "21") (pinfunction "21_21") (pintype "bidirectional"))
    )
    (net (code "167") (name "/EXT9.LVDS_6_P") (class "Default")
      (node (ref "J6") (pin "20") (pinfunction "20_20") (pintype "bidirectional"))
    )
    (net (code "168") (name "/EXT9.LVDS_7_N") (class "Default")
      (node (ref "J6") (pin "24") (pinfunction "24_24") (pintype "bidirectional"))
    )
    (net (code "169") (name "/EXT9.LVDS_7_P") (class "Default")
      (node (ref "J6") (pin "23") (pinfunction "23_23") (pintype "bidirectional"))
    )
    (net (code "170") (name "/EXT10.LVDS_0_N") (class "Default")
      (node (ref "J7") (pin "3") (pinfunction "3_3") (pintype "bidirectional"))
    )
    (net (code "171") (name "/EXT10.LVDS_0_P") (class "Default")
      (node (ref "J7") (pin "2") (pinfunction "2_2") (pintype "bidirectional"))
    )
    (net (code "172") (name "/EXT10.LVDS_1_N") (class "Default")
      (node (ref "J7") (pin "6") (pinfunction "6_6") (pintype "bidirectional"))
    )
    (net (code "173") (name "/EXT10.LVDS_1_P") (class "Default")
      (node (ref "J7") (pin "5") (pinfunction "5_5") (pintype "bidirectional"))
    )
    (net (code "174") (name "/EXT10.LVDS_2_N") (class "Default")
      (node (ref "J7") (pin "9") (pinfunction "9_9") (pintype "bidirectional"))
    )
    (net (code "175") (name "/EXT10.LVDS_2_P") (class "Default")
      (node (ref "J7") (pin "8") (pinfunction "8_8") (pintype "bidirectional"))
    )
    (net (code "176") (name "/EXT10.LVDS_3_N") (class "Default")
      (node (ref "J7") (pin "12") (pinfunction "12_12") (pintype "bidirectional"))
    )
    (net (code "177") (name "/EXT10.LVDS_3_P") (class "Default")
      (node (ref "J7") (pin "11") (pinfunction "11_11") (pintype "bidirectional"))
    )
    (net (code "178") (name "/EXT10.LVDS_4_N") (class "Default")
      (node (ref "J7") (pin "15") (pinfunction "15_15") (pintype "bidirectional"))
    )
    (net (code "179") (name "/EXT10.LVDS_4_P") (class "Default")
      (node (ref "J7") (pin "14") (pinfunction "14_14") (pintype "bidirectional"))
    )
    (net (code "180") (name "/EXT10.LVDS_5_N") (class "Default")
      (node (ref "J7") (pin "18") (pinfunction "18_18") (pintype "bidirectional"))
    )
    (net (code "181") (name "/EXT10.LVDS_5_P") (class "Default")
      (node (ref "J7") (pin "17") (pinfunction "17_17") (pintype "bidirectional"))
    )
    (net (code "182") (name "/EXT10.LVDS_6_N") (class "Default")
      (node (ref "J7") (pin "21") (pinfunction "21_21") (pintype "bidirectional"))
    )
    (net (code "183") (name "/EXT10.LVDS_6_P") (class "Default")
      (node (ref "J7") (pin "20") (pinfunction "20_20") (pintype "bidirectional"))
    )
    (net (code "184") (name "/EXT10.LVDS_7_N") (class "Default")
      (node (ref "J7") (pin "24") (pinfunction "24_24") (pintype "bidirectional"))
    )
    (net (code "185") (name "/EXT10.LVDS_7_P") (class "Default")
      (node (ref "J7") (pin "23") (pinfunction "23_23") (pintype "bidirectional"))
    )
    (net (code "186") (name "/EXT11.LVDS_0_N") (class "Default")
      (node (ref "J17") (pin "3") (pinfunction "3_3") (pintype "bidirectional"))
    )
    (net (code "187") (name "/EXT11.LVDS_0_P") (class "Default")
      (node (ref "J17") (pin "2") (pinfunction "2_2") (pintype "bidirectional"))
    )
    (net (code "188") (name "/EXT11.LVDS_1_N") (class "Default")
      (node (ref "J17") (pin "6") (pinfunction "6_6") (pintype "bidirectional"))
    )
    (net (code "189") (name "/EXT11.LVDS_1_P") (class "Default")
      (node (ref "J17") (pin "5") (pinfunction "5_5") (pintype "bidirectional"))
    )
    (net (code "190") (name "/EXT11.LVDS_2_N") (class "Default")
      (node (ref "J17") (pin "9") (pinfunction "9_9") (pintype "bidirectional"))
    )
    (net (code "191") (name "/EXT11.LVDS_2_P") (class "Default")
      (node (ref "J17") (pin "8") (pinfunction "8_8") (pintype "bidirectional"))
    )
    (net (code "192") (name "/EXT11.LVDS_3_N") (class "Default")
      (node (ref "J17") (pin "12") (pinfunction "12_12") (pintype "bidirectional"))
    )
    (net (code "193") (name "/EXT11.LVDS_3_P") (class "Default")
      (node (ref "J17") (pin "11") (pinfunction "11_11") (pintype "bidirectional"))
    )
    (net (code "194") (name "/EXT11.LVDS_4_N") (class "Default")
      (node (ref "J17") (pin "15") (pinfunction "15_15") (pintype "bidirectional"))
    )
    (net (code "195") (name "/EXT11.LVDS_4_P") (class "Default")
      (node (ref "J17") (pin "14") (pinfunction "14_14") (pintype "bidirectional"))
    )
    (net (code "196") (name "/EXT11.LVDS_5_N") (class "Default")
      (node (ref "J17") (pin "18") (pinfunction "18_18") (pintype "bidirectional"))
    )
    (net (code "197") (name "/EXT11.LVDS_5_P") (class "Default")
      (node (ref "J17") (pin "17") (pinfunction "17_17") (pintype "bidirectional"))
    )
    (net (code "198") (name "/EXT11.LVDS_6_N") (class "Default")
      (node (ref "J17") (pin "21") (pinfunction "21_21") (pintype "bidirectional"))
    )
    (net (code "199") (name "/EXT11.LVDS_6_P") (class "Default")
      (node (ref "J17") (pin "20") (pinfunction "20_20") (pintype "bidirectional"))
    )
    (net (code "200") (name "/EXT11.LVDS_7_N") (class "Default")
      (node (ref "J17") (pin "24") (pinfunction "24_24") (pintype "bidirectional"))
    )
    (net (code "201") (name "/EXT11.LVDS_7_P") (class "Default")
      (node (ref "J17") (pin "23") (pinfunction "23_23") (pintype "bidirectional"))
    )
    (net (code "202") (name "/I2C_SCL_0") (class "Default")
      (node (ref "D3") (pin "3") (pinfunction "I/O2_3") (pintype "bidirectional"))
      (node (ref "J9") (pin "27") (pinfunction "27_27") (pintype "bidirectional"))
    )
    (net (code "203") (name "/I2C_SCL_1") (class "Default")
      (node (ref "D4") (pin "3") (pinfunction "I/O2_3") (pintype "bidirectional"))
      (node (ref "J10") (pin "27") (pinfunction "27_27") (pintype "bidirectional"))
    )
    (net (code "204") (name "/I2C_SCL_2") (class "Default")
      (node (ref "D5") (pin "3") (pinfunction "I/O2_3") (pintype "bidirectional"))
      (node (ref "J11") (pin "27") (pinfunction "27_27") (pintype "bidirectional"))
    )
    (net (code "205") (name "/I2C_SCL_3") (class "Default")
      (node (ref "D6") (pin "3") (pinfunction "I/O2_3") (pintype "bidirectional"))
      (node (ref "J12") (pin "27") (pinfunction "27_27") (pintype "bidirectional"))
    )
    (net (code "206") (name "/I2C_SCL_4") (class "Default")
      (node (ref "D7") (pin "3") (pinfunction "I/O2_3") (pintype "bidirectional"))
      (node (ref "J13") (pin "27") (pinfunction "27_27") (pintype "bidirectional"))
    )
    (net (code "207") (name "/I2C_SCL_5") (class "Default")
      (node (ref "D8") (pin "3") (pinfunction "I/O2_3") (pintype "bidirectional"))
      (node (ref "J14") (pin "27") (pinfunction "27_27") (pintype "bidirectional"))
    )
    (net (code "208") (name "/I2C_SCL_6") (class "Default")
      (node (ref "D9") (pin "3") (pinfunction "I/O2_3") (pintype "bidirectional"))
      (node (ref "J15") (pin "27") (pinfunction "27_27") (pintype "bidirectional"))
    )
    (net (code "209") (name "/I2C_SCL_7") (class "Default")
      (node (ref "D10") (pin "3") (pinfunction "I/O2_3") (pintype "bidirectional"))
      (node (ref "J16") (pin "27") (pinfunction "27_27") (pintype "bidirectional"))
    )
    (net (code "210") (name "/I2C_SCL_8") (class "Default")
      (node (ref "D11") (pin "3") (pinfunction "I/O2_3") (pintype "bidirectional"))
      (node (ref "J5") (pin "27") (pinfunction "27_27") (pintype "bidirectional"))
    )
    (net (code "211") (name "/I2C_SCL_9") (class "Default")
      (node (ref "D13") (pin "3") (pinfunction "I/O2_3") (pintype "bidirectional"))
      (node (ref "J6") (pin "27") (pinfunction "27_27") (pintype "bidirectional"))
    )
    (net (code "212") (name "/I2C_SCL_10") (class "Default")
      (node (ref "D12") (pin "3") (pinfunction "I/O2_3") (pintype "bidirectional"))
      (node (ref "J7") (pin "27") (pinfunction "27_27") (pintype "bidirectional"))
    )
    (net (code "213") (name "/I2C_SCL_11") (class "Default")
      (node (ref "D14") (pin "3") (pinfunction "I/O2_3") (pintype "bidirectional"))
      (node (ref "J17") (pin "27") (pinfunction "27_27") (pintype "bidirectional"))
    )
    (net (code "215") (name "/I2C_SDA_0") (class "Default")
      (node (ref "D3") (pin "2") (pinfunction "I/O1_2") (pintype "bidirectional"))
      (node (ref "J9") (pin "26") (pinfunction "26_26") (pintype "bidirectional"))
    )
    (net (code "216") (name "/I2C_SDA_1") (class "Default")
      (node (ref "D4") (pin "2") (pinfunction "I/O1_2") (pintype "bidirectional"))
      (node (ref "J10") (pin "26") (pinfunction "26_26") (pintype "bidirectional"))
    )
    (net (code "217") (name "/I2C_SDA_2") (class "Default")
      (node (ref "D5") (pin "2") (pinfunction "I/O1_2") (pintype "bidirectional"))
      (node (ref "J11") (pin "26") (pinfunction "26_26") (pintype "bidirectional"))
    )
    (net (code "218") (name "/I2C_SDA_3") (class "Default")
      (node (ref "D6") (pin "2") (pinfunction "I/O1_2") (pintype "bidirectional"))
      (node (ref "J12") (pin "26") (pinfunction "26_26") (pintype "bidirectional"))
    )
    (net (code "219") (name "/I2C_SDA_4") (class "Default")
      (node (ref "D7") (pin "2") (pinfunction "I/O1_2") (pintype "bidirectional"))
      (node (ref "J13") (pin "26") (pinfunction "26_26") (pintype "bidirectional"))
    )
    (net (code "220") (name "/I2C_SDA_5") (class "Default")
      (node (ref "D8") (pin "2") (pinfunction "I/O1_2") (pintype "bidirectional"))
      (node (ref "J14") (pin "26") (pinfunction "26_26") (pintype "bidirectional"))
    )
    (net (code "221") (name "/I2C_SDA_6") (class "Default")
      (node (ref "D9") (pin "2") (pinfunction "I/O1_2") (pintype "bidirectional"))
      (node (ref "J15") (pin "26") (pinfunction "26_26") (pintype "bidirectional"))
    )
    (net (code "222") (name "/I2C_SDA_7") (class "Default")
      (node (ref "D10") (pin "2") (pinfunction "I/O1_2") (pintype "bidirectional"))
      (node (ref "J16") (pin "26") (pinfunction "26_26") (pintype "bidirectional"))
    )
    (net (code "223") (name "/I2C_SDA_8") (class "Default")
      (node (ref "D11") (pin "2") (pinfunction "I/O1_2") (pintype "bidirectional"))
      (node (ref "J5") (pin "26") (pinfunction "26_26") (pintype "bidirectional"))
    )
    (net (code "224") (name "/I2C_SDA_9") (class "Default")
      (node (ref "D13") (pin "2") (pinfunction "I/O1_2") (pintype "bidirectional"))
      (node (ref "J6") (pin "26") (pinfunction "26_26") (pintype "bidirectional"))
    )
    (net (code "225") (name "/I2C_SDA_10") (class "Default")
      (node (ref "D12") (pin "2") (pinfunction "I/O1_2") (pintype "bidirectional"))
      (node (ref "J7") (pin "26") (pinfunction "26_26") (pintype "bidirectional"))
    )
    (net (code "226") (name "/I2C_SDA_11") (class "Default")
      (node (ref "D14") (pin "2") (pinfunction "I/O1_2") (pintype "bidirectional"))
      (node (ref "J17") (pin "26") (pinfunction "26_26") (pintype "bidirectional"))
    )
    (net (code "229") (name "GND") (class "Default")
      (node (ref "C175") (pin "1") (pinfunction "1_1") (pintype "passive"))
      (node (ref "C176") (pin "1") (pinfunction "1_1") (pintype "passive"))
      (node (ref "C177") (pin "1") (pinfunction "1_1") (pintype "passive"))
      (node (ref "C228") (pin "1") (pinfunction "1_1") (pintype "passive"))
      (node (ref "C229") (pin "1") (pinfunction "1_1") (pintype "passive"))
      (node (ref "C230") (pin "1") (pinfunction "1_1") (pintype "passive"))
      (node (ref "C231") (pin "1") (pinfunction "1_1") (pintype "passive"))
      (node (ref "C30") (pin "1") (pinfunction "1_1") (pintype "passive"))
      (node (ref "C31") (pin "1") (pinfunction "1_1") (pintype "passive"))
      (node (ref "C39") (pin "1") (pinfunction "1_1") (pintype "passive"))
      (node (ref "C40") (pin "1") (pinfunction "1_1") (pintype "passive"))
      (node (ref "C42") (pin "1") (pinfunction "1_1") (pintype "passive"))
      (node (ref "D10") (pin "1") (pinfunction "GND_1") (pintype "power_in"))
      (node (ref "D11") (pin "1") (pinfunction "GND_1") (pintype "power_in"))
      (node (ref "D12") (pin "1") (pinfunction "GND_1") (pintype "power_in"))
      (node (ref "D13") (pin "1") (pinfunction "GND_1") (pintype "power_in"))
      (node (ref "D14") (pin "1") (pinfunction "GND_1") (pintype "power_in"))
      (node (ref "D3") (pin "1") (pinfunction "GND_1") (pintype "power_in"))
      (node (ref "D4") (pin "1") (pinfunction "GND_1") (pintype "power_in"))
      (node (ref "D5") (pin "1") (pinfunction "GND_1") (pintype "power_in"))
      (node (ref "D6") (pin "1") (pinfunction "GND_1") (pintype "power_in"))
      (node (ref "D7") (pin "1") (pinfunction "GND_1") (pintype "power_in"))
      (node (ref "D8") (pin "1") (pinfunction "GND_1") (pintype "power_in"))
      (node (ref "D9") (pin "1") (pinfunction "GND_1") (pintype "power_in"))
      (node (ref "J10") (pin "1") (pinfunction "1_1") (pintype "bidirectional"))
      (node (ref "J10") (pin "10") (pinfunction "10_10") (pintype "bidirectional"))
      (node (ref "J10") (pin "13") (pinfunction "13_13") (pintype "bidirectional"))
      (node (ref "J10") (pin "16") (pinfunction "16_16") (pintype "bidirectional"))
      (node (ref "J10") (pin "19") (pinfunction "19_19") (pintype "bidirectional"))
      (node (ref "J10") (pin "22") (pinfunction "22_22") (pintype "bidirectional"))
      (node (ref "J10") (pin "25") (pinfunction "25_25") (pintype "bidirectional"))
      (node (ref "J10") (pin "4") (pinfunction "4_4") (pintype "bidirectional"))
      (node (ref "J10") (pin "7") (pinfunction "7_7") (pintype "bidirectional"))
      (node (ref "J11") (pin "1") (pinfunction "1_1") (pintype "bidirectional"))
      (node (ref "J11") (pin "10") (pinfunction "10_10") (pintype "bidirectional"))
      (node (ref "J11") (pin "13") (pinfunction "13_13") (pintype "bidirectional"))
      (node (ref "J11") (pin "16") (pinfunction "16_16") (pintype "bidirectional"))
      (node (ref "J11") (pin "19") (pinfunction "19_19") (pintype "bidirectional"))
      (node (ref "J11") (pin "22") (pinfunction "22_22") (pintype "bidirectional"))
      (node (ref "J11") (pin "25") (pinfunction "25_25") (pintype "bidirectional"))
      (node (ref "J11") (pin "4") (pinfunction "4_4") (pintype "bidirectional"))
      (node (ref "J11") (pin "7") (pinfunction "7_7") (pintype "bidirectional"))
      (node (ref "J12") (pin "1") (pinfunction "1_1") (pintype "bidirectional"))
      (node (ref "J12") (pin "10") (pinfunction "10_10") (pintype "bidirectional"))
      (node (ref "J12") (pin "13") (pinfunction "13_13") (pintype "bidirectional"))
      (node (ref "J12") (pin "16") (pinfunction "16_16") (pintype "bidirectional"))
      (node (ref "J12") (pin "19") (pinfunction "19_19") (pintype "bidirectional"))
      (node (ref "J12") (pin "22") (pinfunction "22_22") (pintype "bidirectional"))
      (node (ref "J12") (pin "25") (pinfunction "25_25") (pintype "bidirectional"))
      (node (ref "J12") (pin "4") (pinfunction "4_4") (pintype "bidirectional"))
      (node (ref "J12") (pin "7") (pinfunction "7_7") (pintype "bidirectional"))
      (node (ref "J13") (pin "1") (pinfunction "1_1") (pintype "bidirectional"))
      (node (ref "J13") (pin "10") (pinfunction "10_10") (pintype "bidirectional"))
      (node (ref "J13") (pin "13") (pinfunction "13_13") (pintype "bidirectional"))
      (node (ref "J13") (pin "16") (pinfunction "16_16") (pintype "bidirectional"))
      (node (ref "J13") (pin "19") (pinfunction "19_19") (pintype "bidirectional"))
      (node (ref "J13") (pin "22") (pinfunction "22_22") (pintype "bidirectional"))
      (node (ref "J13") (pin "25") (pinfunction "25_25") (pintype "bidirectional"))
      (node (ref "J13") (pin "4") (pinfunction "4_4") (pintype "bidirectional"))
      (node (ref "J13") (pin "7") (pinfunction "7_7") (pintype "bidirectional"))
      (node (ref "J14") (pin "1") (pinfunction "1_1") (pintype "bidirectional"))
      (node (ref "J14") (pin "10") (pinfunction "10_10") (pintype "bidirectional"))
      (node (ref "J14") (pin "13") (pinfunction "13_13") (pintype "bidirectional"))
      (node (ref "J14") (pin "16") (pinfunction "16_16") (pintype "bidirectional"))
      (node (ref "J14") (pin "19") (pinfunction "19_19") (pintype "bidirectional"))
      (node (ref "J14") (pin "22") (pinfunction "22_22") (pintype "bidirectional"))
      (node (ref "J14") (pin "25") (pinfunction "25_25") (pintype "bidirectional"))
      (node (ref "J14") (pin "4") (pinfunction "4_4") (pintype "bidirectional"))
      (node (ref "J14") (pin "7") (pinfunction "7_7") (pintype "bidirectional"))
      (node (ref "J15") (pin "1") (pinfunction "1_1") (pintype "bidirectional"))
      (node (ref "J15") (pin "10") (pinfunction "10_10") (pintype "bidirectional"))
      (node (ref "J15") (pin "13") (pinfunction "13_13") (pintype "bidirectional"))
      (node (ref "J15") (pin "16") (pinfunction "16_16") (pintype "bidirectional"))
      (node (ref "J15") (pin "19") (pinfunction "19_19") (pintype "bidirectional"))
      (node (ref "J15") (pin "22") (pinfunction "22_22") (pintype "bidirectional"))
      (node (ref "J15") (pin "25") (pinfunction "25_25") (pintype "bidirectional"))
      (node (ref "J15") (pin "4") (pinfunction "4_4") (pintype "bidirectional"))
      (node (ref "J15") (pin "7") (pinfunction "7_7") (pintype "bidirectional"))
      (node (ref "J16") (pin "1") (pinfunction "1_1") (pintype "bidirectional"))
      (node (ref "J16") (pin "10") (pinfunction "10_10") (pintype "bidirectional"))
      (node (ref "J16") (pin "13") (pinfunction "13_13") (pintype "bidirectional"))
      (node (ref "J16") (pin "16") (pinfunction "16_16") (pintype "bidirectional"))
      (node (ref "J16") (pin "19") (pinfunction "19_19") (pintype "bidirectional"))
      (node (ref "J16") (pin "22") (pinfunction "22_22") (pintype "bidirectional"))
      (node (ref "J16") (pin "25") (pinfunction "25_25") (pintype "bidirectional"))
      (node (ref "J16") (pin "4") (pinfunction "4_4") (pintype "bidirectional"))
      (node (ref "J16") (pin "7") (pinfunction "7_7") (pintype "bidirectional"))
      (node (ref "J17") (pin "1") (pinfunction "1_1") (pintype "bidirectional"))
      (node (ref "J17") (pin "10") (pinfunction "10_10") (pintype "bidirectional"))
      (node (ref "J17") (pin "13") (pinfunction "13_13") (pintype "bidirectional"))
      (node (ref "J17") (pin "16") (pinfunction "16_16") (pintype "bidirectional"))
      (node (ref "J17") (pin "19") (pinfunction "19_19") (pintype "bidirectional"))
      (node (ref "J17") (pin "22") (pinfunction "22_22") (pintype "bidirectional"))
      (node (ref "J17") (pin "25") (pinfunction "25_25") (pintype "bidirectional"))
      (node (ref "J17") (pin "4") (pinfunction "4_4") (pintype "bidirectional"))
      (node (ref "J17") (pin "7") (pinfunction "7_7") (pintype "bidirectional"))
      (node (ref "J5") (pin "1") (pinfunction "1_1") (pintype "bidirectional"))
      (node (ref "J5") (pin "10") (pinfunction "10_10") (pintype "bidirectional"))
      (node (ref "J5") (pin "13") (pinfunction "13_13") (pintype "bidirectional"))
      (node (ref "J5") (pin "16") (pinfunction "16_16") (pintype "bidirectional"))
      (node (ref "J5") (pin "19") (pinfunction "19_19") (pintype "bidirectional"))
      (node (ref "J5") (pin "22") (pinfunction "22_22") (pintype "bidirectional"))
      (node (ref "J5") (pin "25") (pinfunction "25_25") (pintype "bidirectional"))
      (node (ref "J5") (pin "4") (pinfunction "4_4") (pintype "bidirectional"))
      (node (ref "J5") (pin "7") (pinfunction "7_7") (pintype "bidirectional"))
      (node (ref "J6") (pin "1") (pinfunction "1_1") (pintype "bidirectional"))
      (node (ref "J6") (pin "10") (pinfunction "10_10") (pintype "bidirectional"))
      (node (ref "J6") (pin "13") (pinfunction "13_13") (pintype "bidirectional"))
      (node (ref "J6") (pin "16") (pinfunction "16_16") (pintype "bidirectional"))
      (node (ref "J6") (pin "19") (pinfunction "19_19") (pintype "bidirectional"))
      (node (ref "J6") (pin "22") (pinfunction "22_22") (pintype "bidirectional"))
      (node (ref "J6") (pin "25") (pinfunction "25_25") (pintype "bidirectional"))
      (node (ref "J6") (pin "4") (pinfunction "4_4") (pintype "bidirectional"))
      (node (ref "J6") (pin "7") (pinfunction "7_7") (pintype "bidirectional"))
      (node (ref "J7") (pin "1") (pinfunction "1_1") (pintype "bidirectional"))
      (node (ref "J7") (pin "10") (pinfunction "10_10") (pintype "bidirectional"))
      (node (ref "J7") (pin "13") (pinfunction "13_13") (pintype "bidirectional"))
      (node (ref "J7") (pin "16") (pinfunction "16_16") (pintype "bidirectional"))
      (node (ref "J7") (pin "19") (pinfunction "19_19") (pintype "bidirectional"))
      (node (ref "J7") (pin "22") (pinfunction "22_22") (pintype "bidirectional"))
      (node (ref "J7") (pin "25") (pinfunction "25_25") (pintype "bidirectional"))
      (node (ref "J7") (pin "4") (pinfunction "4_4") (pintype "bidirectional"))
      (node (ref "J7") (pin "7") (pinfunction "7_7") (pintype "bidirectional"))
      (node (ref "J9") (pin "1") (pinfunction "1_1") (pintype "bidirectional"))
      (node (ref "J9") (pin "10") (pinfunction "10_10") (pintype "bidirectional"))
      (node (ref "J9") (pin "13") (pinfunction "13_13") (pintype "bidirectional"))
      (node (ref "J9") (pin "16") (pinfunction "16_16") (pintype "bidirectional"))
      (node (ref "J9") (pin "19") (pinfunction "19_19") (pintype "bidirectional"))
      (node (ref "J9") (pin "22") (pinfunction "22_22") (pintype "bidirectional"))
      (node (ref "J9") (pin "25") (pinfunction "25_25") (pintype "bidirectional"))
      (node (ref "J9") (pin "4") (pinfunction "4_4") (pintype "bidirectional"))
      (node (ref "J9") (pin "7") (pinfunction "7_7") (pintype "bidirectional"))
    )
    (net (code "230") (name "Net-(F1-Pad2)") (class "Default")
      (node (ref "F1") (pin "2") (pinfunction "2_2") (pintype "passive"))
      (node (ref "J10") (pin "30") (pinfunction "30_30") (pintype "bidirectional"))
      (node (ref "J11") (pin "30") (pinfunction "30_30") (pintype "bidirectional"))
      (node (ref "J12") (pin "30") (pinfunction "30_30") (pintype "bidirectional"))
      (node (ref "J9") (pin "30") (pinfunction "30_30") (pintype "bidirectional"))
    )
    (net (code "231") (name "Net-(F2-Pad2)") (class "Default")
      (node (ref "F2") (pin "2") (pinfunction "2_2") (pintype "passive"))
      (node (ref "J13") (pin "30") (pinfunction "30_30") (pintype "bidirectional"))
      (node (ref "J14") (pin "30") (pinfunction "30_30") (pintype "bidirectional"))
      (node (ref "J15") (pin "30") (pinfunction "30_30") (pintype "bidirectional"))
      (node (ref "J16") (pin "30") (pinfunction "30_30") (pintype "bidirectional"))
    )
    (net (code "232") (name "Net-(F3-Pad2)") (class "Default")
      (node (ref "F3") (pin "2") (pinfunction "2_2") (pintype "passive"))
      (node (ref "J17") (pin "30") (pinfunction "30_30") (pintype "bidirectional"))
      (node (ref "J5") (pin "30") (pinfunction "30_30") (pintype "bidirectional"))
      (node (ref "J6") (pin "30") (pinfunction "30_30") (pintype "bidirectional"))
      (node (ref "J7") (pin "30") (pinfunction "30_30") (pintype "bidirectional"))
    )
    (net (code "233") (name "P3V3") (class "Default")
      (node (ref "C175") (pin "2") (pinfunction "2_2") (pintype "passive"))
      (node (ref "C176") (pin "2") (pinfunction "2_2") (pintype "passive"))
      (node (ref "C177") (pin "2") (pinfunction "2_2") (pintype "passive"))
      (node (ref "C228") (pin "2") (pinfunction "2_2") (pintype "passive"))
      (node (ref "C229") (pin "2") (pinfunction "2_2") (pintype "passive"))
      (node (ref "C230") (pin "2") (pinfunction "2_2") (pintype "passive"))
      (node (ref "C231") (pin "2") (pinfunction "2_2") (pintype "passive"))
      (node (ref "C30") (pin "2") (pinfunction "2_2") (pintype "passive"))
      (node (ref "C31") (pin "2") (pinfunction "2_2") (pintype "passive"))
      (node (ref "C39") (pin "2") (pinfunction "2_2") (pintype "passive"))
      (node (ref "C40") (pin "2") (pinfunction "2_2") (pintype "passive"))
      (node (ref "C42") (pin "2") (pinfunction "2_2") (pintype "passive"))
      (node (ref "D10") (pin "4") (pinfunction "VCC_4") (pintype "power_in"))
      (node (ref "D11") (pin "4") (pinfunction "VCC_4") (pintype "power_in"))
      (node (ref "D12") (pin "4") (pinfunction "VCC_4") (pintype "power_in"))
      (node (ref "D13") (pin "4") (pinfunction "VCC_4") (pintype "power_in"))
      (node (ref "D14") (pin "4") (pinfunction "VCC_4") (pintype "power_in"))
      (node (ref "D3") (pin "4") (pinfunction "VCC_4") (pintype "power_in"))
      (node (ref "D4") (pin "4") (pinfunction "VCC_4") (pintype "power_in"))
      (node (ref "D5") (pin "4") (pinfunction "VCC_4") (pintype "power_in"))
      (node (ref "D6") (pin "4") (pinfunction "VCC_4") (pintype "power_in"))
      (node (ref "D7") (pin "4") (pinfunction "VCC_4") (pintype "power_in"))
      (node (ref "D8") (pin "4") (pinfunction "VCC_4") (pintype "power_in"))
      (node (ref "D9") (pin "4") (pinfunction "VCC_4") (pintype "power_in"))
      (node (ref "F1") (pin "1") (pinfunction "1_1") (pintype "passive"))
      (node (ref "F2") (pin "1") (pinfunction "1_1") (pintype "passive"))
      (node (ref "F3") (pin "1") (pinfunction "1_1") (pintype "passive"))
    )
    (net (code "234") (name "P12V0") (class "Default")
      (node (ref "J10") (pin "28") (pinfunction "28_28") (pintype "bidirectional"))
      (node (ref "J10") (pin "29") (pinfunction "29_29") (pintype "bidirectional"))
      (node (ref "J11") (pin "28") (pinfunction "28_28") (pintype "bidirectional"))
      (node (ref "J11") (pin "29") (pinfunction "29_29") (pintype "bidirectional"))
      (node (ref "J12") (pin "28") (pinfunction "28_28") (pintype "bidirectional"))
      (node (ref "J12") (pin "29") (pinfunction "29_29") (pintype "bidirectional"))
      (node (ref "J13") (pin "28") (pinfunction "28_28") (pintype "bidirectional"))
      (node (ref "J13") (pin "29") (pinfunction "29_29") (pintype "bidirectional"))
      (node (ref "J14") (pin "28") (pinfunction "28_28") (pintype "bidirectional"))
      (node (ref "J14") (pin "29") (pinfunction "29_29") (pintype "bidirectional"))
      (node (ref "J15") (pin "28") (pinfunction "28_28") (pintype "bidirectional"))
      (node (ref "J15") (pin "29") (pinfunction "29_29") (pintype "bidirectional"))
      (node (ref "J16") (pin "28") (pinfunction "28_28") (pintype "bidirectional"))
      (node (ref "J16") (pin "29") (pinfunction "29_29") (pintype "bidirectional"))
      (node (ref "J17") (pin "28") (pinfunction "28_28") (pintype "bidirectional"))
      (node (ref "J17") (pin "29") (pinfunction "29_29") (pintype "bidirectional"))
      (node (ref "J5") (pin "28") (pinfunction "28_28") (pintype "bidirectional"))
      (node (ref "J5") (pin "29") (pinfunction "29_29") (pintype "bidirectional"))
      (node (ref "J6") (pin "28") (pinfunction "28_28") (pintype "bidirectional"))
      (node (ref "J6") (pin "29") (pinfunction "29_29") (pintype "bidirectional"))
      (node (ref "J7") (pin "28") (pinfunction "28_28") (pintype "bidirectional"))
      (node (ref "J7") (pin "29") (pinfunction "29_29") (pintype "bidirectional"))
      (node (ref "J9") (pin "28") (pinfunction "28_28") (pintype "bidirectional"))
      (node (ref "J9") (pin "29") (pinfunction "29_29") (pintype "bidirectional"))
    )
  )
)
